# CMC_PPG.net
KiCad netlist of a schematic drawn in EAGLE
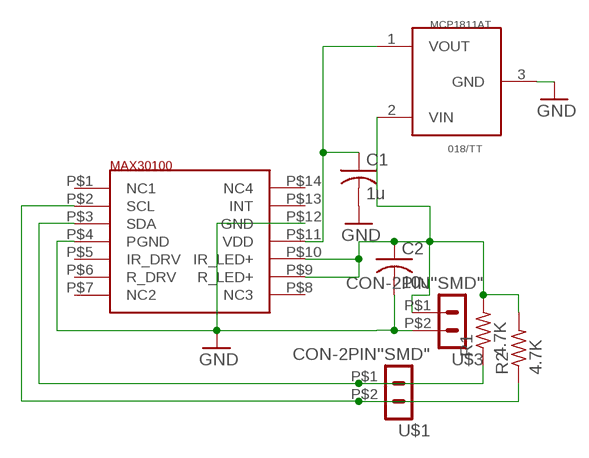
[diagram p0: schematic, sheet 1]

(export (version "E")
  (design (tool "Eeschema 10.0.6"))
  (components
    (comp (ref "C1")
      (value "1u")
      (footprint "eagle-import:C0805")
      (libsource (lib "eagle-import") (part "C-USC0805"))
    )
    (comp (ref "C2")
      (value "10u")
      (footprint "eagle-import:C0805")
      (libsource (lib "eagle-import") (part "C-USC0805"))
    )
    (comp (ref "R1")
      (value "4.7K")
      (footprint "eagle-import:R0603")
      (libsource (lib "eagle-import") (part "R-US_R0603"))
    )
    (comp (ref "R2")
      (value "4.7K")
      (footprint "eagle-import:R0603")
      (libsource (lib "eagle-import") (part "R-US_R0603"))
    )
    (comp (ref "U$1")
      (value "CON-2PIN''SMD\"")
      (footprint "eagle-import:CON-2PINSMD")
      (libsource (lib "eagle-import") (part "CON-2PIN''SMD{dblquote}"))
    )
    (comp (ref "U$2")
      (value "OPTO_OXI_MAX30100")
      (footprint "eagle-import:OPTO_OXI_MAX30100")
      (libsource (lib "eagle-import") (part "OPTO_OXI_MAX30100"))
    )
    (comp (ref "U$3")
      (value "CON-2PIN''SMD\"")
      (footprint "eagle-import:CON-2PINSMD")
      (libsource (lib "eagle-import") (part "CON-2PIN''SMD{dblquote}"))
    )
    (comp (ref "U$4")
      (value "MCP1811AT-018/TTSMD")
      (footprint "eagle-import:SOT23-3")
      (libsource (lib "eagle-import") (part "MCP1811AT-018/TTSMD"))
    )
  )
  (nets
    (net (code "1") (name "GND") (class "Default")
      (node (ref "C1") (pin "2") (pinfunction "2_2") (pintype "passive"))
      (node (ref "C2") (pin "2") (pinfunction "2_2") (pintype "passive"))
      (node (ref "U$2") (pin "P$12") (pinfunction "GND_P$12") (pintype "bidirectional"))
      (node (ref "U$2") (pin "P$4") (pinfunction "PGND_P$4") (pintype "bidirectional"))
      (node (ref "U$3") (pin "P$2") (pinfunction "2_P$2") (pintype "passive"))
      (node (ref "U$4") (pin "3") (pinfunction "GND_3") (pintype "bidirectional"))
    )
    (net (code "2") (name "Net-(U$1-1)") (class "Default")
      (node (ref "R1") (pin "1") (pinfunction "1_1") (pintype "passive"))
      (node (ref "U$1") (pin "P$1") (pinfunction "1_P$1") (pintype "passive"))
      (node (ref "U$2") (pin "P$3") (pinfunction "SDA_P$3") (pintype "bidirectional"))
    )
    (net (code "3") (name "Net-(U$1-2)") (class "Default")
      (node (ref "R2") (pin "1") (pinfunction "1_1") (pintype "passive"))
      (node (ref "U$1") (pin "P$2") (pinfunction "2_P$2") (pintype "passive"))
      (node (ref "U$2") (pin "P$2") (pinfunction "SCL_P$2") (pintype "bidirectional"))
    )
    (net (code "4") (name "Net-(U$2-IR_LED+)") (class "Default")
      (node (ref "C2") (pin "1") (pinfunction "1_1") (pintype "passive"))
      (node (ref "R1") (pin "2") (pinfunction "2_2") (pintype "passive"))
      (node (ref "R2") (pin "2") (pinfunction "2_2") (pintype "passive"))
      (node (ref "U$2") (pin "P$10") (pinfunction "IR_LED+_P$10") (pintype "bidirectional"))
      (node (ref "U$2") (pin "P$9") (pinfunction "R_LED+_P$9") (pintype "bidirectional"))
      (node (ref "U$3") (pin "P$1") (pinfunction "1_P$1") (pintype "passive"))
      (node (ref "U$4") (pin "2") (pinfunction "VIN_2") (pintype "bidirectional"))
    )
    (net (code "5") (name "Net-(U$2-VDD)") (class "Default")
      (node (ref "C1") (pin "1") (pinfunction "1_1") (pintype "passive"))
      (node (ref "U$2") (pin "P$11") (pinfunction "VDD_P$11") (pintype "bidirectional"))
      (node (ref "U$4") (pin "1") (pinfunction "VOUT_1") (pintype "bidirectional"))
    )
    (net (code "6") (name "unconnected-(U$2-INT-PadP$13)") (class "Default")
      (node (ref "U$2") (pin "P$13") (pinfunction "INT_P$13") (pintype "bidirectional"))
    )
    (net (code "7") (name "unconnected-(U$2-IR_DRV-PadP$5)") (class "Default")
      (node (ref "U$2") (pin "P$5") (pinfunction "IR_DRV_P$5") (pintype "bidirectional"))
    )
    (net (code "8") (name "unconnected-(U$2-NC1-PadP$1)") (class "Default")
      (node (ref "U$2") (pin "P$1") (pinfunction "NC1_P$1") (pintype "bidirectional"))
    )
    (net (code "9") (name "unconnected-(U$2-NC2-PadP$7)") (class "Default")
      (node (ref "U$2") (pin "P$7") (pinfunction "NC2_P$7") (pintype "bidirectional"))
    )
    (net (code "10") (name "unconnected-(U$2-NC3-PadP$8)") (class "Default")
      (node (ref "U$2") (pin "P$8") (pinfunction "NC3_P$8") (pintype "bidirectional"))
    )
    (net (code "11") (name "unconnected-(U$2-NC4-PadP$14)") (class "Default")
      (node (ref "U$2") (pin "P$14") (pinfunction "NC4_P$14") (pintype "bidirectional"))
    )
    (net (code "12") (name "unconnected-(U$2-R_DRV-PadP$6)") (class "Default")
      (node (ref "U$2") (pin "P$6") (pinfunction "R_DRV_P$6") (pintype "bidirectional"))
    )
  )
)
